# uCamShield.net
KiCad netlist of a schematic drawn in EAGLE
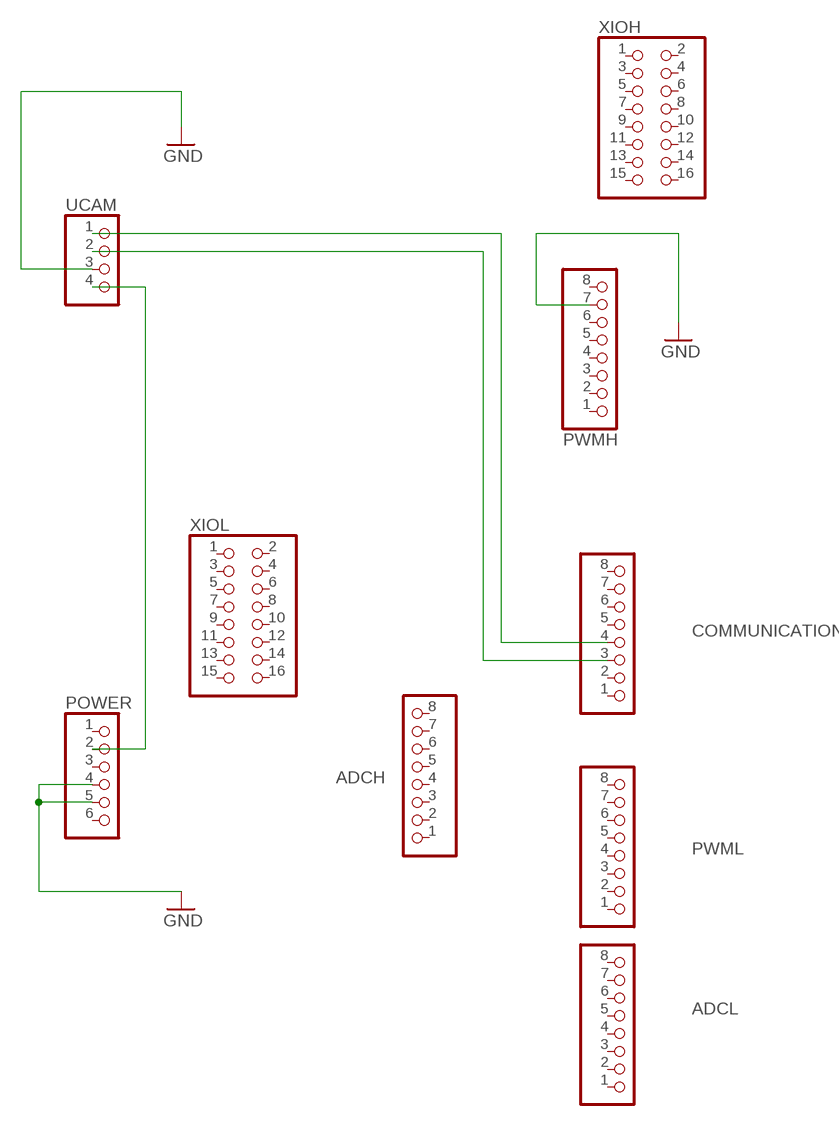
[diagram p0: schematic, sheet 1]

(export (version "E")
  (design (tool "Eeschema 10.0.6"))
  (components
    (comp (ref "ADCH")
      (value "PINHD-1X8")
      (footprint "eagle-import:1X08")
      (libsource (lib "eagle-import") (part "PINHD-1X8"))
    )
    (comp (ref "ADCL")
      (value "PINHD-1X8")
      (footprint "eagle-import:1X08")
      (libsource (lib "eagle-import") (part "PINHD-1X8"))
    )
    (comp (ref "COMMUNICATION")
      (value "PINHD-1X8")
      (footprint "eagle-import:1X08")
      (libsource (lib "eagle-import") (part "PINHD-1X8"))
    )
    (comp (ref "POWER")
      (value "PINHD-1X6")
      (footprint "eagle-import:1X06")
      (libsource (lib "eagle-import") (part "PINHD-1X6"))
    )
    (comp (ref "PWMH")
      (value "PINHD-1X8")
      (footprint "eagle-import:1X08")
      (libsource (lib "eagle-import") (part "PINHD-1X8"))
    )
    (comp (ref "PWML")
      (value "PINHD-1X8")
      (footprint "eagle-import:1X08")
      (libsource (lib "eagle-import") (part "PINHD-1X8"))
    )
    (comp (ref "UCAM")
      (value "PINHD-1X4")
      (footprint "eagle-import:1X04")
      (libsource (lib "eagle-import") (part "PINHD-1X4"))
    )
    (comp (ref "XIOH")
      (value "PINHD-2X8")
      (footprint "eagle-import:2X08")
      (libsource (lib "eagle-import") (part "PINHD-2X8"))
    )
    (comp (ref "XIOL")
      (value "PINHD-2X8")
      (footprint "eagle-import:2X08")
      (libsource (lib "eagle-import") (part "PINHD-2X8"))
    )
  )
  (nets
    (net (code "1") (name "GND") (class "Default")
      (node (ref "POWER") (pin "4") (pinfunction "4_4") (pintype "passive"))
      (node (ref "POWER") (pin "5") (pinfunction "5_5") (pintype "passive"))
      (node (ref "PWMH") (pin "7") (pinfunction "7_7") (pintype "passive"))
      (node (ref "UCAM") (pin "3") (pinfunction "3_3") (pintype "passive"))
    )
    (net (code "2") (name "Net-(COMMUNICATION-Pad3)") (class "Default")
      (node (ref "COMMUNICATION") (pin "3") (pinfunction "3_3") (pintype "passive"))
      (node (ref "UCAM") (pin "2") (pinfunction "2_2") (pintype "passive"))
    )
    (net (code "3") (name "Net-(COMMUNICATION-Pad4)") (class "Default")
      (node (ref "COMMUNICATION") (pin "4") (pinfunction "4_4") (pintype "passive"))
      (node (ref "UCAM") (pin "1") (pinfunction "1_1") (pintype "passive"))
    )
    (net (code "4") (name "Net-(POWER-Pad2)") (class "Default")
      (node (ref "POWER") (pin "2") (pinfunction "2_2") (pintype "passive"))
      (node (ref "UCAM") (pin "4") (pinfunction "4_4") (pintype "passive"))
    )
    (net (code "5") (name "unconnected-(ADCH-Pad1)") (class "Default")
      (node (ref "ADCH") (pin "1") (pinfunction "1_1") (pintype "passive"))
    )
    (net (code "6") (name "unconnected-(ADCH-Pad2)") (class "Default")
      (node (ref "ADCH") (pin "2") (pinfunction "2_2") (pintype "passive"))
    )
    (net (code "7") (name "unconnected-(ADCH-Pad3)") (class "Default")
      (node (ref "ADCH") (pin "3") (pinfunction "3_3") (pintype "passive"))
    )
    (net (code "8") (name "unconnected-(ADCH-Pad4)") (class "Default")
      (node (ref "ADCH") (pin "4") (pinfunction "4_4") (pintype "passive"))
    )
    (net (code "9") (name "unconnected-(ADCH-Pad5)") (class "Default")
      (node (ref "ADCH") (pin "5") (pinfunction "5_5") (pintype "passive"))
    )
    (net (code "10") (name "unconnected-(ADCH-Pad6)") (class "Default")
      (node (ref "ADCH") (pin "6") (pinfunction "6_6") (pintype "passive"))
    )
    (net (code "11") (name "unconnected-(ADCH-Pad7)") (class "Default")
      (node (ref "ADCH") (pin "7") (pinfunction "7_7") (pintype "passive"))
    )
    (net (code "12") (name "unconnected-(ADCH-Pad8)") (class "Default")
      (node (ref "ADCH") (pin "8") (pinfunction "8_8") (pintype "passive"))
    )
    (net (code "13") (name "unconnected-(ADCL-Pad1)") (class "Default")
      (node (ref "ADCL") (pin "1") (pinfunction "1_1") (pintype "passive"))
    )
    (net (code "14") (name "unconnected-(ADCL-Pad2)") (class "Default")
      (node (ref "ADCL") (pin "2") (pinfunction "2_2") (pintype "passive"))
    )
    (net (code "15") (name "unconnected-(ADCL-Pad3)") (class "Default")
      (node (ref "ADCL") (pin "3") (pinfunction "3_3") (pintype "passive"))
    )
    (net (code "16") (name "unconnected-(ADCL-Pad4)") (class "Default")
      (node (ref "ADCL") (pin "4") (pinfunction "4_4") (pintype "passive"))
    )
    (net (code "17") (name "unconnected-(ADCL-Pad5)") (class "Default")
      (node (ref "ADCL") (pin "5") (pinfunction "5_5") (pintype "passive"))
    )
    (net (code "18") (name "unconnected-(ADCL-Pad6)") (class "Default")
      (node (ref "ADCL") (pin "6") (pinfunction "6_6") (pintype "passive"))
    )
    (net (code "19") (name "unconnected-(ADCL-Pad7)") (class "Default")
      (node (ref "ADCL") (pin "7") (pinfunction "7_7") (pintype "passive"))
    )
    (net (code "20") (name "unconnected-(ADCL-Pad8)") (class "Default")
      (node (ref "ADCL") (pin "8") (pinfunction "8_8") (pintype "passive"))
    )
    (net (code "21") (name "unconnected-(COMMUNICATION-Pad1)") (class "Default")
      (node (ref "COMMUNICATION") (pin "1") (pinfunction "1_1") (pintype "passive"))
    )
    (net (code "22") (name "unconnected-(COMMUNICATION-Pad2)") (class "Default")
      (node (ref "COMMUNICATION") (pin "2") (pinfunction "2_2") (pintype "passive"))
    )
    (net (code "23") (name "unconnected-(COMMUNICATION-Pad5)") (class "Default")
      (node (ref "COMMUNICATION") (pin "5") (pinfunction "5_5") (pintype "passive"))
    )
    (net (code "24") (name "unconnected-(COMMUNICATION-Pad6)") (class "Default")
      (node (ref "COMMUNICATION") (pin "6") (pinfunction "6_6") (pintype "passive"))
    )
    (net (code "25") (name "unconnected-(COMMUNICATION-Pad7)") (class "Default")
      (node (ref "COMMUNICATION") (pin "7") (pinfunction "7_7") (pintype "passive"))
    )
    (net (code "26") (name "unconnected-(COMMUNICATION-Pad8)") (class "Default")
      (node (ref "COMMUNICATION") (pin "8") (pinfunction "8_8") (pintype "passive"))
    )
    (net (code "27") (name "unconnected-(POWER-Pad1)") (class "Default")
      (node (ref "POWER") (pin "1") (pinfunction "1_1") (pintype "passive"))
    )
    (net (code "28") (name "unconnected-(POWER-Pad3)") (class "Default")
      (node (ref "POWER") (pin "3") (pinfunction "3_3") (pintype "passive"))
    )
    (net (code "29") (name "unconnected-(POWER-Pad6)") (class "Default")
      (node (ref "POWER") (pin "6") (pinfunction "6_6") (pintype "passive"))
    )
    (net (code "30") (name "unconnected-(PWMH-Pad1)") (class "Default")
      (node (ref "PWMH") (pin "1") (pinfunction "1_1") (pintype "passive"))
    )
    (net (code "31") (name "unconnected-(PWMH-Pad2)") (class "Default")
      (node (ref "PWMH") (pin "2") (pinfunction "2_2") (pintype "passive"))
    )
    (net (code "32") (name "unconnected-(PWMH-Pad3)") (class "Default")
      (node (ref "PWMH") (pin "3") (pinfunction "3_3") (pintype "passive"))
    )
    (net (code "33") (name "unconnected-(PWMH-Pad4)") (class "Default")
      (node (ref "PWMH") (pin "4") (pinfunction "4_4") (pintype "passive"))
    )
    (net (code "34") (name "unconnected-(PWMH-Pad5)") (class "Default")
      (node (ref "PWMH") (pin "5") (pinfunction "5_5") (pintype "passive"))
    )
    (net (code "35") (name "unconnected-(PWMH-Pad6)") (class "Default")
      (node (ref "PWMH") (pin "6") (pinfunction "6_6") (pintype "passive"))
    )
    (net (code "36") (name "unconnected-(PWMH-Pad8)") (class "Default")
      (node (ref "PWMH") (pin "8") (pinfunction "8_8") (pintype "passive"))
    )
    (net (code "37") (name "unconnected-(PWML-Pad1)") (class "Default")
      (node (ref "PWML") (pin "1") (pinfunction "1_1") (pintype "passive"))
    )
    (net (code "38") (name "unconnected-(PWML-Pad2)") (class "Default")
      (node (ref "PWML") (pin "2") (pinfunction "2_2") (pintype "passive"))
    )
    (net (code "39") (name "unconnected-(PWML-Pad3)") (class "Default")
      (node (ref "PWML") (pin "3") (pinfunction "3_3") (pintype "passive"))
    )
    (net (code "40") (name "unconnected-(PWML-Pad4)") (class "Default")
      (node (ref "PWML") (pin "4") (pinfunction "4_4") (pintype "passive"))
    )
    (net (code "41") (name "unconnected-(PWML-Pad5)") (class "Default")
      (node (ref "PWML") (pin "5") (pinfunction "5_5") (pintype "passive"))
    )
    (net (code "42") (name "unconnected-(PWML-Pad6)") (class "Default")
      (node (ref "PWML") (pin "6") (pinfunction "6_6") (pintype "passive"))
    )
    (net (code "43") (name "unconnected-(PWML-Pad7)") (class "Default")
      (node (ref "PWML") (pin "7") (pinfunction "7_7") (pintype "passive"))
    )
    (net (code "44") (name "unconnected-(PWML-Pad8)") (class "Default")
      (node (ref "PWML") (pin "8") (pinfunction "8_8") (pintype "passive"))
    )
    (net (code "45") (name "unconnected-(XIOH-Pad1)") (class "Default")
      (node (ref "XIOH") (pin "1") (pinfunction "1_1") (pintype "passive"))
    )
    (net (code "46") (name "unconnected-(XIOH-Pad2)") (class "Default")
      (node (ref "XIOH") (pin "2") (pinfunction "2_2") (pintype "passive"))
    )
    (net (code "47") (name "unconnected-(XIOH-Pad3)") (class "Default")
      (node (ref "XIOH") (pin "3") (pinfunction "3_3") (pintype "passive"))
    )
    (net (code "48") (name "unconnected-(XIOH-Pad4)") (class "Default")
      (node (ref "XIOH") (pin "4") (pinfunction "4_4") (pintype "passive"))
    )
    (net (code "49") (name "unconnected-(XIOH-Pad5)") (class "Default")
      (node (ref "XIOH") (pin "5") (pinfunction "5_5") (pintype "passive"))
    )
    (net (code "50") (name "unconnected-(XIOH-Pad6)") (class "Default")
      (node (ref "XIOH") (pin "6") (pinfunction "6_6") (pintype "passive"))
    )
    (net (code "51") (name "unconnected-(XIOH-Pad7)") (class "Default")
      (node (ref "XIOH") (pin "7") (pinfunction "7_7") (pintype "passive"))
    )
    (net (code "52") (name "unconnected-(XIOH-Pad8)") (class "Default")
      (node (ref "XIOH") (pin "8") (pinfunction "8_8") (pintype "passive"))
    )
    (net (code "53") (name "unconnected-(XIOH-Pad9)") (class "Default")
      (node (ref "XIOH") (pin "9") (pinfunction "9_9") (pintype "passive"))
    )
    (net (code "54") (name "unconnected-(XIOH-Pad10)") (class "Default")
      (node (ref "XIOH") (pin "10") (pinfunction "10_10") (pintype "passive"))
    )
    (net (code "55") (name "unconnected-(XIOH-Pad11)") (class "Default")
      (node (ref "XIOH") (pin "11") (pinfunction "11_11") (pintype "passive"))
    )
    (net (code "56") (name "unconnected-(XIOH-Pad12)") (class "Default")
      (node (ref "XIOH") (pin "12") (pinfunction "12_12") (pintype "passive"))
    )
    (net (code "57") (name "unconnected-(XIOH-Pad13)") (class "Default")
      (node (ref "XIOH") (pin "13") (pinfunction "13_13") (pintype "passive"))
    )
    (net (code "58") (name "unconnected-(XIOH-Pad14)") (class "Default")
      (node (ref "XIOH") (pin "14") (pinfunction "14_14") (pintype "passive"))
    )
    (net (code "59") (name "unconnected-(XIOH-Pad15)") (class "Default")
      (node (ref "XIOH") (pin "15") (pinfunction "15_15") (pintype "passive"))
    )
    (net (code "60") (name "unconnected-(XIOH-Pad16)") (class "Default")
      (node (ref "XIOH") (pin "16") (pinfunction "16_16") (pintype "passive"))
    )
    (net (code "61") (name "unconnected-(XIOL-Pad1)") (class "Default")
      (node (ref "XIOL") (pin "1") (pinfunction "1_1") (pintype "passive"))
    )
    (net (code "62") (name "unconnected-(XIOL-Pad2)") (class "Default")
      (node (ref "XIOL") (pin "2") (pinfunction "2_2") (pintype "passive"))
    )
    (net (code "63") (name "unconnected-(XIOL-Pad3)") (class "Default")
      (node (ref "XIOL") (pin "3") (pinfunction "3_3") (pintype "passive"))
    )
    (net (code "64") (name "unconnected-(XIOL-Pad4)") (class "Default")
      (node (ref "XIOL") (pin "4") (pinfunction "4_4") (pintype "passive"))
    )
    (net (code "65") (name "unconnected-(XIOL-Pad5)") (class "Default")
      (node (ref "XIOL") (pin "5") (pinfunction "5_5") (pintype "passive"))
    )
    (net (code "66") (name "unconnected-(XIOL-Pad6)") (class "Default")
      (node (ref "XIOL") (pin "6") (pinfunction "6_6") (pintype "passive"))
    )
    (net (code "67") (name "unconnected-(XIOL-Pad7)") (class "Default")
      (node (ref "XIOL") (pin "7") (pinfunction "7_7") (pintype "passive"))
    )
    (net (code "68") (name "unconnected-(XIOL-Pad8)") (class "Default")
      (node (ref "XIOL") (pin "8") (pinfunction "8_8") (pintype "passive"))
    )
    (net (code "69") (name "unconnected-(XIOL-Pad9)") (class "Default")
      (node (ref "XIOL") (pin "9") (pinfunction "9_9") (pintype "passive"))
    )
    (net (code "70") (name "unconnected-(XIOL-Pad10)") (class "Default")
      (node (ref "XIOL") (pin "10") (pinfunction "10_10") (pintype "passive"))
    )
    (net (code "71") (name "unconnected-(XIOL-Pad11)") (class "Default")
      (node (ref "XIOL") (pin "11") (pinfunction "11_11") (pintype "passive"))
    )
    (net (code "72") (name "unconnected-(XIOL-Pad12)") (class "Default")
      (node (ref "XIOL") (pin "12") (pinfunction "12_12") (pintype "passive"))
    )
    (net (code "73") (name "unconnected-(XIOL-Pad13)") (class "Default")
      (node (ref "XIOL") (pin "13") (pinfunction "13_13") (pintype "passive"))
    )
    (net (code "74") (name "unconnected-(XIOL-Pad14)") (class "Default")
      (node (ref "XIOL") (pin "14") (pinfunction "14_14") (pintype "passive"))
    )
    (net (code "75") (name "unconnected-(XIOL-Pad15)") (class "Default")
      (node (ref "XIOL") (pin "15") (pinfunction "15_15") (pintype "passive"))
    )
    (net (code "76") (name "unconnected-(XIOL-Pad16)") (class "Default")
      (node (ref "XIOL") (pin "16") (pinfunction "16_16") (pintype "passive"))
    )
  )
)
